# 452BRG.net
KiCad netlist of a schematic drawn in EAGLE
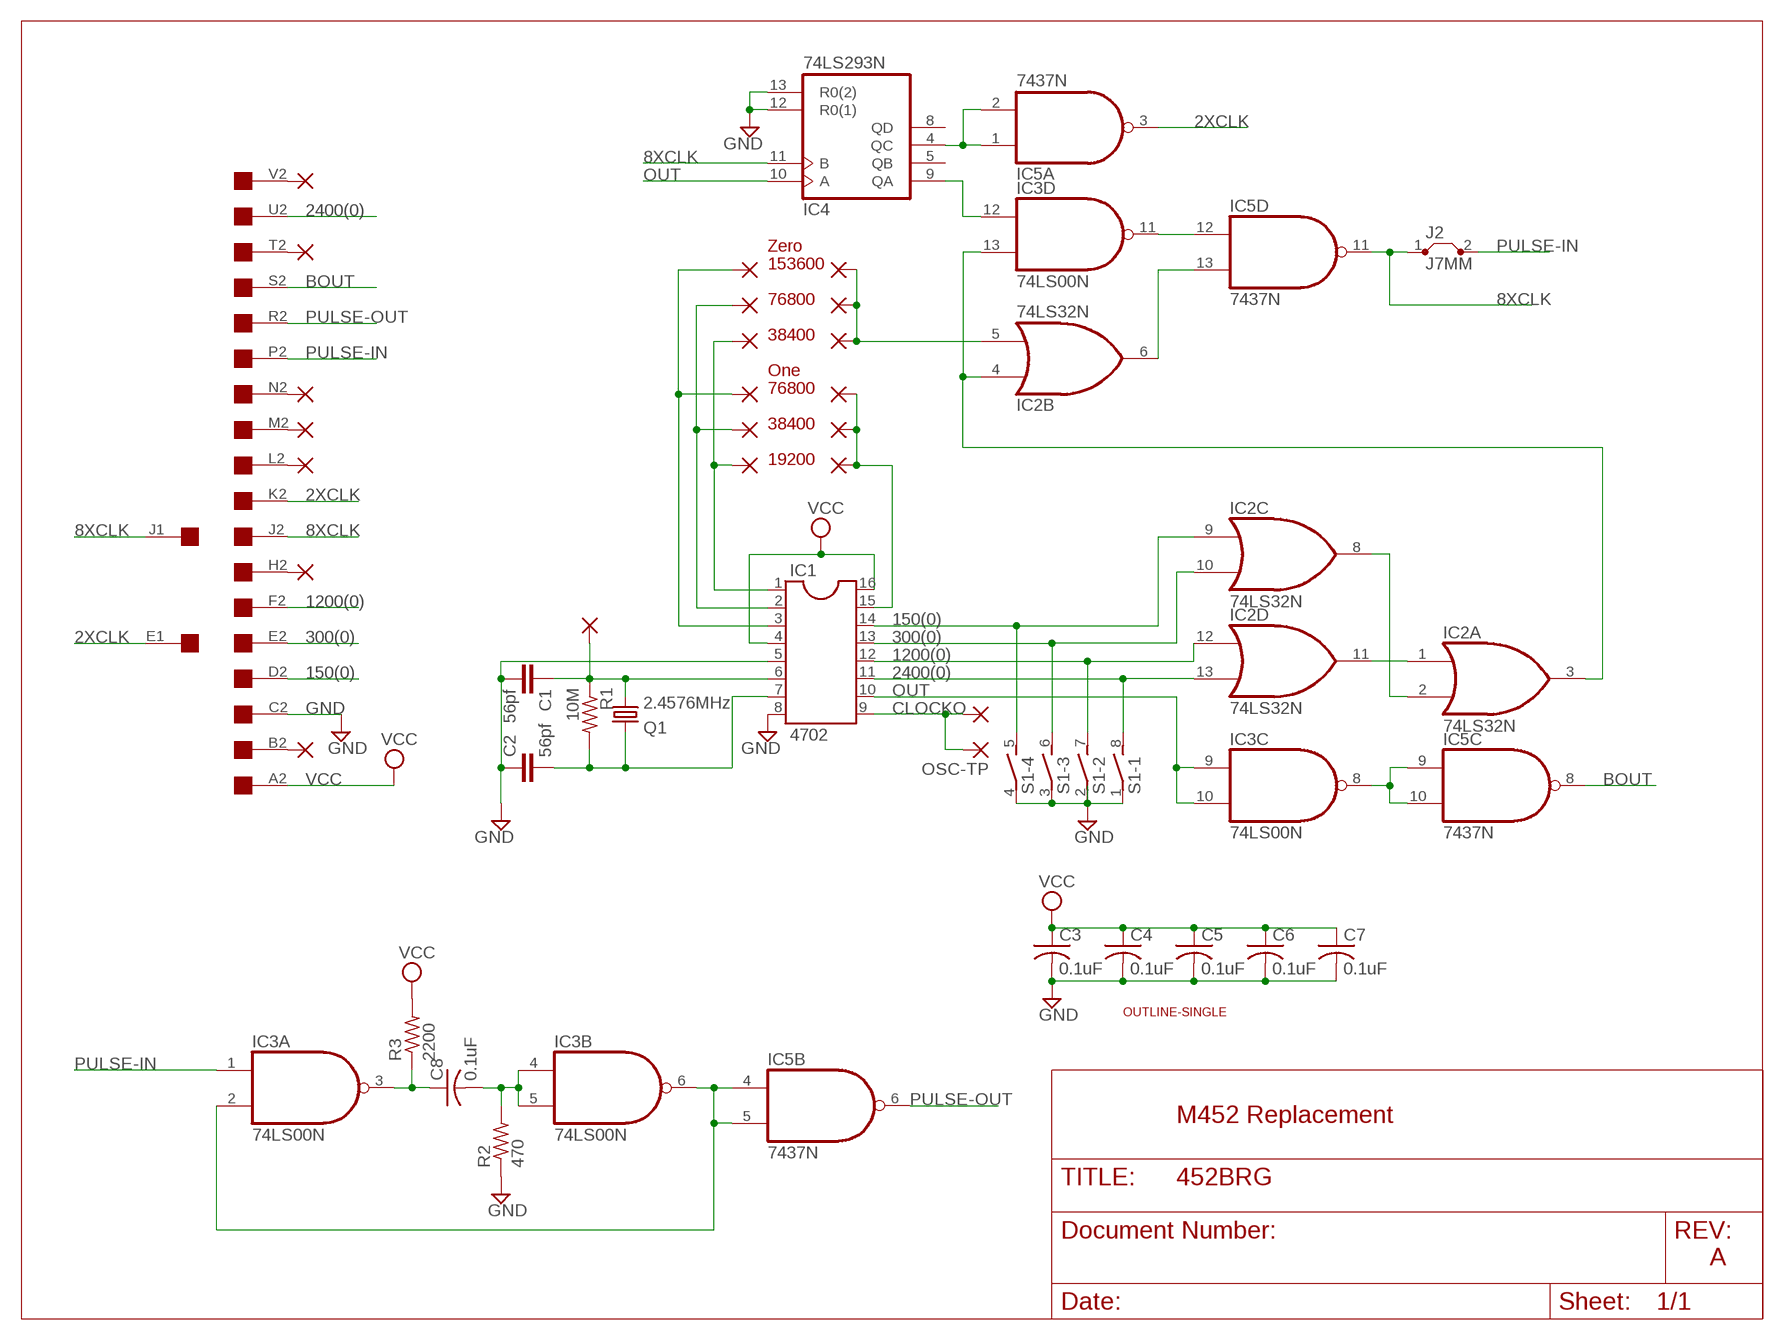
[diagram p0: schematic, sheet 1]

(export (version "E")
  (design (tool "Eeschema 10.0.6"))
  (components
    (comp (ref "C1")
      (value "56pf")
      (footprint "eagle-import:C075-032X103")
      (libsource (lib "eagle-import") (part "C-EU075-032X103"))
    )
    (comp (ref "C2")
      (value "56pf")
      (footprint "eagle-import:C075-032X103")
      (libsource (lib "eagle-import") (part "C-EU075-032X103"))
    )
    (comp (ref "C3")
      (value "0.1uF")
      (footprint "eagle-import:C075-032X103")
      (libsource (lib "eagle-import") (part "C-US075-032X103"))
    )
    (comp (ref "C4")
      (value "0.1uF")
      (footprint "eagle-import:C075-032X103")
      (libsource (lib "eagle-import") (part "C-US075-032X103"))
    )
    (comp (ref "C5")
      (value "0.1uF")
      (footprint "eagle-import:C075-032X103")
      (libsource (lib "eagle-import") (part "C-US075-032X103"))
    )
    (comp (ref "C6")
      (value "0.1uF")
      (footprint "eagle-import:C075-032X103")
      (libsource (lib "eagle-import") (part "C-US075-032X103"))
    )
    (comp (ref "C7")
      (value "0.1uF")
      (footprint "eagle-import:C075-032X103")
      (libsource (lib "eagle-import") (part "C-US075-032X103"))
    )
    (comp (ref "C8")
      (value "0.1uF")
      (footprint "eagle-import:C075-032X103")
      (libsource (lib "eagle-import") (part "C-US075-032X103"))
    )
    (comp (ref "IC1")
      (value "4702")
      (footprint "eagle-import:DIL16")
      (libsource (lib "eagle-import") (part "DIL16"))
    )
    (comp (ref "IC2")
      (value "74LS32N")
      (footprint "eagle-import:DIL14")
      (libsource (lib "eagle-import") (part "7432NLS"))
    )
    (comp (ref "IC3")
      (value "74LS00N")
      (footprint "eagle-import:DIL14")
      (libsource (lib "eagle-import") (part "7400NLS"))
    )
    (comp (ref "IC4")
      (value "74LS293N")
      (footprint "eagle-import:DIL14")
      (libsource (lib "eagle-import") (part "74293NLS"))
    )
    (comp (ref "IC5")
      (value "7437N")
      (footprint "eagle-import:DIL14")
      (libsource (lib "eagle-import") (part "7437N"))
    )
    (comp (ref "J2")
      (value "J7MM")
      (footprint "eagle-import:07")
      (libsource (lib "eagle-import") (part "J7MM"))
    )
    (comp (ref "OSC-TP")
      (value "1,6/0,8")
      (footprint "eagle-import:1,6_0,8")
      (libsource (lib "eagle-import") (part "1,6/0,8"))
    )
    (comp (ref "PAD1")
      (value "1,6/0,8")
      (footprint "eagle-import:1,6_0,8")
      (libsource (lib "eagle-import") (part "1,6/0,8"))
    )
    (comp (ref "PAD2")
      (value "1,6/0,8")
      (footprint "eagle-import:1,6_0,8")
      (libsource (lib "eagle-import") (part "1,6/0,8"))
    )
    (comp (ref "PAD3")
      (value "1,6/0,8")
      (footprint "eagle-import:1,6_0,8")
      (libsource (lib "eagle-import") (part "1,6/0,8"))
    )
    (comp (ref "PAD4")
      (value "1,6/0,8")
      (footprint "eagle-import:1,6_0,8")
      (libsource (lib "eagle-import") (part "1,6/0,8"))
    )
    (comp (ref "PAD5")
      (value "1,6/0,8")
      (footprint "eagle-import:1,6_0,8")
      (libsource (lib "eagle-import") (part "1,6/0,8"))
    )
    (comp (ref "PAD6")
      (value "1,6/0,8")
      (footprint "eagle-import:1,6_0,8")
      (libsource (lib "eagle-import") (part "1,6/0,8"))
    )
    (comp (ref "PAD7")
      (value "1,6/0,8")
      (footprint "eagle-import:1,6_0,8")
      (libsource (lib "eagle-import") (part "1,6/0,8"))
    )
    (comp (ref "PAD8")
      (value "1,6/0,8")
      (footprint "eagle-import:1,6_0,8")
      (libsource (lib "eagle-import") (part "1,6/0,8"))
    )
    (comp (ref "PAD9")
      (value "1,6/0,8")
      (footprint "eagle-import:1,6_0,8")
      (libsource (lib "eagle-import") (part "1,6/0,8"))
    )
    (comp (ref "PAD10")
      (value "1,6/0,8")
      (footprint "eagle-import:1,6_0,8")
      (libsource (lib "eagle-import") (part "1,6/0,8"))
    )
    (comp (ref "PAD11")
      (value "1,6/0,8")
      (footprint "eagle-import:1,6_0,8")
      (libsource (lib "eagle-import") (part "1,6/0,8"))
    )
    (comp (ref "PAD12")
      (value "1,6/0,8")
      (footprint "eagle-import:1,6_0,8")
      (libsource (lib "eagle-import") (part "1,6/0,8"))
    )
    (comp (ref "PAD13")
      (value "1,6/0,8")
      (footprint "eagle-import:1,6_0,8")
      (libsource (lib "eagle-import") (part "1,6/0,8"))
    )
    (comp (ref "PAD14")
      (value "1,6/0,8")
      (footprint "eagle-import:1,6_0,8")
      (libsource (lib "eagle-import") (part "1,6/0,8"))
    )
    (comp (ref "PAD15")
      (value "1,6/0,8")
      (footprint "eagle-import:1,6_0,8")
      (libsource (lib "eagle-import") (part "1,6/0,8"))
    )
    (comp (ref "PAD16")
      (value "1,6/0,8")
      (footprint "eagle-import:1,6_0,8")
      (libsource (lib "eagle-import") (part "1,6/0,8"))
    )
    (comp (ref "PAD17")
      (value "1,6/0,8")
      (footprint "eagle-import:1,6_0,8")
      (libsource (lib "eagle-import") (part "1,6/0,8"))
    )
    (comp (ref "PAD18")
      (value "1,6/0,8")
      (footprint "eagle-import:1,6_0,8")
      (libsource (lib "eagle-import") (part "1,6/0,8"))
    )
    (comp (ref "PAD19")
      (value "1,6/0,8")
      (footprint "eagle-import:1,6_0,8")
      (libsource (lib "eagle-import") (part "1,6/0,8"))
    )
    (comp (ref "PAD20")
      (value "1,6/0,8")
      (footprint "eagle-import:1,6_0,8")
      (libsource (lib "eagle-import") (part "1,6/0,8"))
    )
    (comp (ref "Q1")
      (value "2.4576MHz")
      (footprint "eagle-import:HC49U-H")
      (libsource (lib "eagle-import") (part "CRYSTALHC49U-H"))
    )
    (comp (ref "R1")
      (value "10M")
      (footprint "eagle-import:0207_10")
      (libsource (lib "eagle-import") (part "R-US_0207/10"))
    )
    (comp (ref "R2")
      (value "470")
      (footprint "eagle-import:0207_12")
      (libsource (lib "eagle-import") (part "R-US_0207/12"))
    )
    (comp (ref "R3")
      (value "2200")
      (footprint "eagle-import:0207_15")
      (libsource (lib "eagle-import") (part "R-US_0207/15"))
    )
    (comp (ref "S1")
      (value "DIP04S")
      (footprint "eagle-import:DIP04S")
      (libsource (lib "eagle-import") (part "DIP04S"))
    )
    (comp (ref "U$2")
      (value "SINGLE")
      (footprint "eagle-import:EDGE-CON2")
      (libsource (lib "eagle-import") (part "SINGLE"))
    )
    (comp (ref "U$3")
      (value "OUTLINE-SINGLE")
      (footprint "eagle-import:SINGLE")
      (libsource (lib "eagle-import") (part "OUTLINE-SINGLE"))
    )
    (comp (ref "XTAL")
      (value "1,6/0,8")
      (footprint "eagle-import:1,6_0,8")
      (libsource (lib "eagle-import") (part "1,6/0,8"))
    )
  )
  (nets
    (net (code "1") (name "/2XCLK") (class "Default")
      (node (ref "IC5") (pin "3") (pinfunction "O_3") (pintype "output"))
      (node (ref "U$2") (pin "E1") (pinfunction "1_E1") (pintype "bidirectional"))
      (node (ref "U$2") (pin "K2") (pinfunction "1_K2") (pintype "bidirectional"))
    )
    (net (code "2") (name "/8XCLK") (class "Default")
      (node (ref "IC4") (pin "11") (pinfunction "B_11") (pintype "input"))
      (node (ref "IC5") (pin "11") (pinfunction "O_11") (pintype "output"))
      (node (ref "J2") (pin "1") (pinfunction "1_1") (pintype "passive"))
      (node (ref "U$2") (pin "J1") (pinfunction "1_J1") (pintype "bidirectional"))
      (node (ref "U$2") (pin "J2") (pinfunction "1_J2") (pintype "bidirectional"))
    )
    (net (code "3") (name "/150(0)") (class "Default")
      (node (ref "IC1") (pin "14") (pinfunction "14_14") (pintype "passive"))
      (node (ref "IC2") (pin "9") (pinfunction "I0_9") (pintype "input"))
      (node (ref "S1") (pin "5") (pinfunction "2_5") (pintype "passive"))
      (node (ref "U$2") (pin "D2") (pinfunction "1_D2") (pintype "bidirectional"))
    )
    (net (code "4") (name "/300(0)") (class "Default")
      (node (ref "IC1") (pin "13") (pinfunction "13_13") (pintype "passive"))
      (node (ref "IC2") (pin "10") (pinfunction "I1_10") (pintype "input"))
      (node (ref "S1") (pin "6") (pinfunction "2_6") (pintype "passive"))
      (node (ref "U$2") (pin "E2") (pinfunction "1_E2") (pintype "bidirectional"))
    )
    (net (code "5") (name "/1200(0)") (class "Default")
      (node (ref "IC1") (pin "12") (pinfunction "12_12") (pintype "passive"))
      (node (ref "IC2") (pin "12") (pinfunction "I0_12") (pintype "input"))
      (node (ref "S1") (pin "7") (pinfunction "2_7") (pintype "passive"))
      (node (ref "U$2") (pin "F2") (pinfunction "1_F2") (pintype "bidirectional"))
    )
    (net (code "6") (name "/2400(0)") (class "Default")
      (node (ref "IC1") (pin "11") (pinfunction "11_11") (pintype "passive"))
      (node (ref "IC2") (pin "13") (pinfunction "I1_13") (pintype "input"))
      (node (ref "S1") (pin "8") (pinfunction "2_8") (pintype "passive"))
      (node (ref "U$2") (pin "U2") (pinfunction "1_U2") (pintype "bidirectional"))
    )
    (net (code "7") (name "/BOUT") (class "Default")
      (node (ref "IC5") (pin "8") (pinfunction "O_8") (pintype "output"))
      (node (ref "U$2") (pin "S2") (pinfunction "1_S2") (pintype "bidirectional"))
    )
    (net (code "8") (name "/CLOCKO") (class "Default")
      (node (ref "IC1") (pin "9") (pinfunction "9_9") (pintype "passive"))
      (node (ref "OSC-TP") (pin "1") (pinfunction "P_1") (pintype "passive"))
      (node (ref "PAD20") (pin "1") (pinfunction "P_1") (pintype "passive"))
    )
    (net (code "9") (name "/OUT") (class "Default")
      (node (ref "IC1") (pin "10") (pinfunction "10_10") (pintype "passive"))
      (node (ref "IC3") (pin "10") (pinfunction "I1_10") (pintype "input"))
      (node (ref "IC3") (pin "9") (pinfunction "I0_9") (pintype "input"))
      (node (ref "IC4") (pin "10") (pinfunction "A_10") (pintype "input"))
    )
    (net (code "10") (name "/PULSE-IN") (class "Default")
      (node (ref "IC3") (pin "1") (pinfunction "I0_1") (pintype "input"))
      (node (ref "J2") (pin "2") (pinfunction "2_2") (pintype "passive"))
      (node (ref "U$2") (pin "P2") (pinfunction "1_P2") (pintype "bidirectional"))
    )
    (net (code "11") (name "/PULSE-OUT") (class "Default")
      (node (ref "IC5") (pin "6") (pinfunction "O_6") (pintype "output"))
      (node (ref "U$2") (pin "R2") (pinfunction "1_R2") (pintype "bidirectional"))
    )
    (net (code "12") (name "GND") (class "Default")
      (node (ref "C1") (pin "2") (pinfunction "2_2") (pintype "passive"))
      (node (ref "C2") (pin "1") (pinfunction "1_1") (pintype "passive"))
      (node (ref "C3") (pin "2") (pinfunction "2_2") (pintype "passive"))
      (node (ref "C4") (pin "2") (pinfunction "2_2") (pintype "passive"))
      (node (ref "C5") (pin "2") (pinfunction "2_2") (pintype "passive"))
      (node (ref "C6") (pin "2") (pinfunction "2_2") (pintype "passive"))
      (node (ref "C7") (pin "2") (pinfunction "2_2") (pintype "passive"))
      (node (ref "IC1") (pin "5") (pinfunction "5_5") (pintype "passive"))
      (node (ref "IC1") (pin "8") (pinfunction "8_8") (pintype "passive"))
      (node (ref "IC4") (pin "12") (pinfunction "R0(1)_12") (pintype "input"))
      (node (ref "IC4") (pin "13") (pinfunction "R0(2)_13") (pintype "input"))
      (node (ref "R2") (pin "1") (pinfunction "1_1") (pintype "passive"))
      (node (ref "S1") (pin "1") (pinfunction "1_1") (pintype "passive"))
      (node (ref "S1") (pin "2") (pinfunction "1_2") (pintype "passive"))
      (node (ref "S1") (pin "3") (pinfunction "1_3") (pintype "passive"))
      (node (ref "S1") (pin "4") (pinfunction "1_4") (pintype "passive"))
      (node (ref "U$2") (pin "C2") (pinfunction "1_C2") (pintype "bidirectional"))
    )
    (net (code "13") (name "Net-(C2-Pad2)") (class "Default")
      (node (ref "C2") (pin "2") (pinfunction "2_2") (pintype "passive"))
      (node (ref "IC1") (pin "7") (pinfunction "7_7") (pintype "passive"))
      (node (ref "Q1") (pin "1") (pinfunction "1_1") (pintype "passive"))
      (node (ref "R1") (pin "2") (pinfunction "2_2") (pintype "passive"))
    )
    (net (code "14") (name "Net-(IC2A-I0)") (class "Default")
      (node (ref "IC2") (pin "1") (pinfunction "I0_1") (pintype "input"))
      (node (ref "IC2") (pin "11") (pinfunction "O_11") (pintype "output"))
    )
    (net (code "15") (name "Net-(IC2A-I1)") (class "Default")
      (node (ref "IC2") (pin "2") (pinfunction "I1_2") (pintype "input"))
      (node (ref "IC2") (pin "8") (pinfunction "O_8") (pintype "output"))
    )
    (net (code "16") (name "Net-(IC2A-O)") (class "Default")
      (node (ref "IC2") (pin "3") (pinfunction "O_3") (pintype "output"))
      (node (ref "IC2") (pin "4") (pinfunction "I0_4") (pintype "input"))
      (node (ref "IC3") (pin "13") (pinfunction "I1_13") (pintype "input"))
    )
    (net (code "17") (name "Net-(IC2B-I1)") (class "Default")
      (node (ref "IC2") (pin "5") (pinfunction "I1_5") (pintype "input"))
      (node (ref "PAD10") (pin "1") (pinfunction "P_1") (pintype "passive"))
      (node (ref "PAD11") (pin "1") (pinfunction "P_1") (pintype "passive"))
      (node (ref "PAD12") (pin "1") (pinfunction "P_1") (pintype "passive"))
    )
    (net (code "18") (name "Net-(IC2B-O)") (class "Default")
      (node (ref "IC2") (pin "6") (pinfunction "O_6") (pintype "output"))
      (node (ref "IC5") (pin "13") (pinfunction "I1_13") (pintype "input"))
    )
    (net (code "19") (name "Net-(IC3A-I1)") (class "Default")
      (node (ref "IC3") (pin "2") (pinfunction "I1_2") (pintype "input"))
      (node (ref "IC3") (pin "6") (pinfunction "O_6") (pintype "output"))
      (node (ref "IC5") (pin "4") (pinfunction "I0_4") (pintype "input"))
      (node (ref "IC5") (pin "5") (pinfunction "I1_5") (pintype "input"))
    )
    (net (code "20") (name "Net-(IC3A-O)") (class "Default")
      (node (ref "C8") (pin "1") (pinfunction "1_1") (pintype "passive"))
      (node (ref "IC3") (pin "3") (pinfunction "O_3") (pintype "output"))
      (node (ref "R3") (pin "1") (pinfunction "1_1") (pintype "passive"))
    )
    (net (code "21") (name "Net-(IC3B-I0)") (class "Default")
      (node (ref "C8") (pin "2") (pinfunction "2_2") (pintype "passive"))
      (node (ref "IC3") (pin "4") (pinfunction "I0_4") (pintype "input"))
      (node (ref "IC3") (pin "5") (pinfunction "I1_5") (pintype "input"))
      (node (ref "R2") (pin "2") (pinfunction "2_2") (pintype "passive"))
    )
    (net (code "22") (name "Net-(IC3C-O)") (class "Default")
      (node (ref "IC3") (pin "8") (pinfunction "O_8") (pintype "output"))
      (node (ref "IC5") (pin "10") (pinfunction "I1_10") (pintype "input"))
      (node (ref "IC5") (pin "9") (pinfunction "I0_9") (pintype "input"))
    )
    (net (code "23") (name "Net-(IC3D-I0)") (class "Default")
      (node (ref "IC3") (pin "12") (pinfunction "I0_12") (pintype "input"))
      (node (ref "IC4") (pin "9") (pinfunction "QA_9") (pintype "output"))
    )
    (net (code "24") (name "Net-(IC3D-O)") (class "Default")
      (node (ref "IC3") (pin "11") (pinfunction "O_11") (pintype "output"))
      (node (ref "IC5") (pin "12") (pinfunction "I0_12") (pintype "input"))
    )
    (net (code "25") (name "Net-(IC4A-QC)") (class "Default")
      (node (ref "IC4") (pin "4") (pinfunction "QC_4") (pintype "output"))
      (node (ref "IC5") (pin "1") (pinfunction "I0_1") (pintype "input"))
      (node (ref "IC5") (pin "2") (pinfunction "I1_2") (pintype "input"))
    )
    (net (code "26") (name "Net-(PAD1-P)") (class "Default")
      (node (ref "IC1") (pin "3") (pinfunction "3_3") (pintype "passive"))
      (node (ref "PAD1") (pin "1") (pinfunction "P_1") (pintype "passive"))
      (node (ref "PAD7") (pin "1") (pinfunction "P_1") (pintype "passive"))
    )
    (net (code "27") (name "Net-(PAD2-P)") (class "Default")
      (node (ref "IC1") (pin "2") (pinfunction "2_2") (pintype "passive"))
      (node (ref "PAD2") (pin "1") (pinfunction "P_1") (pintype "passive"))
      (node (ref "PAD8") (pin "1") (pinfunction "P_1") (pintype "passive"))
    )
    (net (code "28") (name "Net-(PAD3-P)") (class "Default")
      (node (ref "IC1") (pin "1") (pinfunction "1_1") (pintype "passive"))
      (node (ref "PAD3") (pin "1") (pinfunction "P_1") (pintype "passive"))
      (node (ref "PAD9") (pin "1") (pinfunction "P_1") (pintype "passive"))
    )
    (net (code "29") (name "Net-(PAD4-P)") (class "Default")
      (node (ref "IC1") (pin "15") (pinfunction "15_15") (pintype "passive"))
      (node (ref "PAD4") (pin "1") (pinfunction "P_1") (pintype "passive"))
      (node (ref "PAD5") (pin "1") (pinfunction "P_1") (pintype "passive"))
      (node (ref "PAD6") (pin "1") (pinfunction "P_1") (pintype "passive"))
    )
    (net (code "30") (name "Net-(PAD13-P)") (class "Default")
      (node (ref "PAD13") (pin "1") (pinfunction "P_1") (pintype "passive"))
      (node (ref "U$2") (pin "V2") (pinfunction "1_V2") (pintype "bidirectional"))
    )
    (net (code "31") (name "Net-(PAD14-P)") (class "Default")
      (node (ref "PAD14") (pin "1") (pinfunction "P_1") (pintype "passive"))
      (node (ref "U$2") (pin "T2") (pinfunction "1_T2") (pintype "bidirectional"))
    )
    (net (code "32") (name "Net-(PAD15-P)") (class "Default")
      (node (ref "PAD15") (pin "1") (pinfunction "P_1") (pintype "passive"))
      (node (ref "U$2") (pin "N2") (pinfunction "1_N2") (pintype "bidirectional"))
    )
    (net (code "33") (name "Net-(PAD16-P)") (class "Default")
      (node (ref "PAD16") (pin "1") (pinfunction "P_1") (pintype "passive"))
      (node (ref "U$2") (pin "M2") (pinfunction "1_M2") (pintype "bidirectional"))
    )
    (net (code "34") (name "Net-(PAD17-P)") (class "Default")
      (node (ref "PAD17") (pin "1") (pinfunction "P_1") (pintype "passive"))
      (node (ref "U$2") (pin "L2") (pinfunction "1_L2") (pintype "bidirectional"))
    )
    (net (code "35") (name "Net-(PAD18-P)") (class "Default")
      (node (ref "PAD18") (pin "1") (pinfunction "P_1") (pintype "passive"))
      (node (ref "U$2") (pin "H2") (pinfunction "1_H2") (pintype "bidirectional"))
    )
    (net (code "36") (name "Net-(PAD19-P)") (class "Default")
      (node (ref "PAD19") (pin "1") (pinfunction "P_1") (pintype "passive"))
      (node (ref "U$2") (pin "B2") (pinfunction "1_B2") (pintype "bidirectional"))
    )
    (net (code "37") (name "Net-(XTAL-P)") (class "Default")
      (node (ref "C1") (pin "1") (pinfunction "1_1") (pintype "passive"))
      (node (ref "IC1") (pin "6") (pinfunction "6_6") (pintype "passive"))
      (node (ref "Q1") (pin "2") (pinfunction "2_2") (pintype "passive"))
      (node (ref "R1") (pin "1") (pinfunction "1_1") (pintype "passive"))
      (node (ref "XTAL") (pin "1") (pinfunction "P_1") (pintype "passive"))
    )
    (net (code "38") (name "VCC") (class "Default")
      (node (ref "C3") (pin "1") (pinfunction "1_1") (pintype "passive"))
      (node (ref "C4") (pin "1") (pinfunction "1_1") (pintype "passive"))
      (node (ref "C5") (pin "1") (pinfunction "1_1") (pintype "passive"))
      (node (ref "C6") (pin "1") (pinfunction "1_1") (pintype "passive"))
      (node (ref "C7") (pin "1") (pinfunction "1_1") (pintype "passive"))
      (node (ref "IC1") (pin "16") (pinfunction "16_16") (pintype "passive"))
      (node (ref "IC1") (pin "4") (pinfunction "4_4") (pintype "passive"))
      (node (ref "R3") (pin "2") (pinfunction "2_2") (pintype "passive"))
      (node (ref "U$2") (pin "A2") (pinfunction "1_A2") (pintype "bidirectional"))
    )
    (net (code "39") (name "unconnected-(IC4A-QB-Pad5)") (class "Default")
      (node (ref "IC4") (pin "5") (pinfunction "QB_5") (pintype "output"))
    )
    (net (code "40") (name "unconnected-(IC4A-QD-Pad8)") (class "Default")
      (node (ref "IC4") (pin "8") (pinfunction "QD_8") (pintype "output"))
    )
  )
)
